# Differential_AS5048_Encoder_Schematic.net
KiCad netlist of a schematic drawn in EAGLE
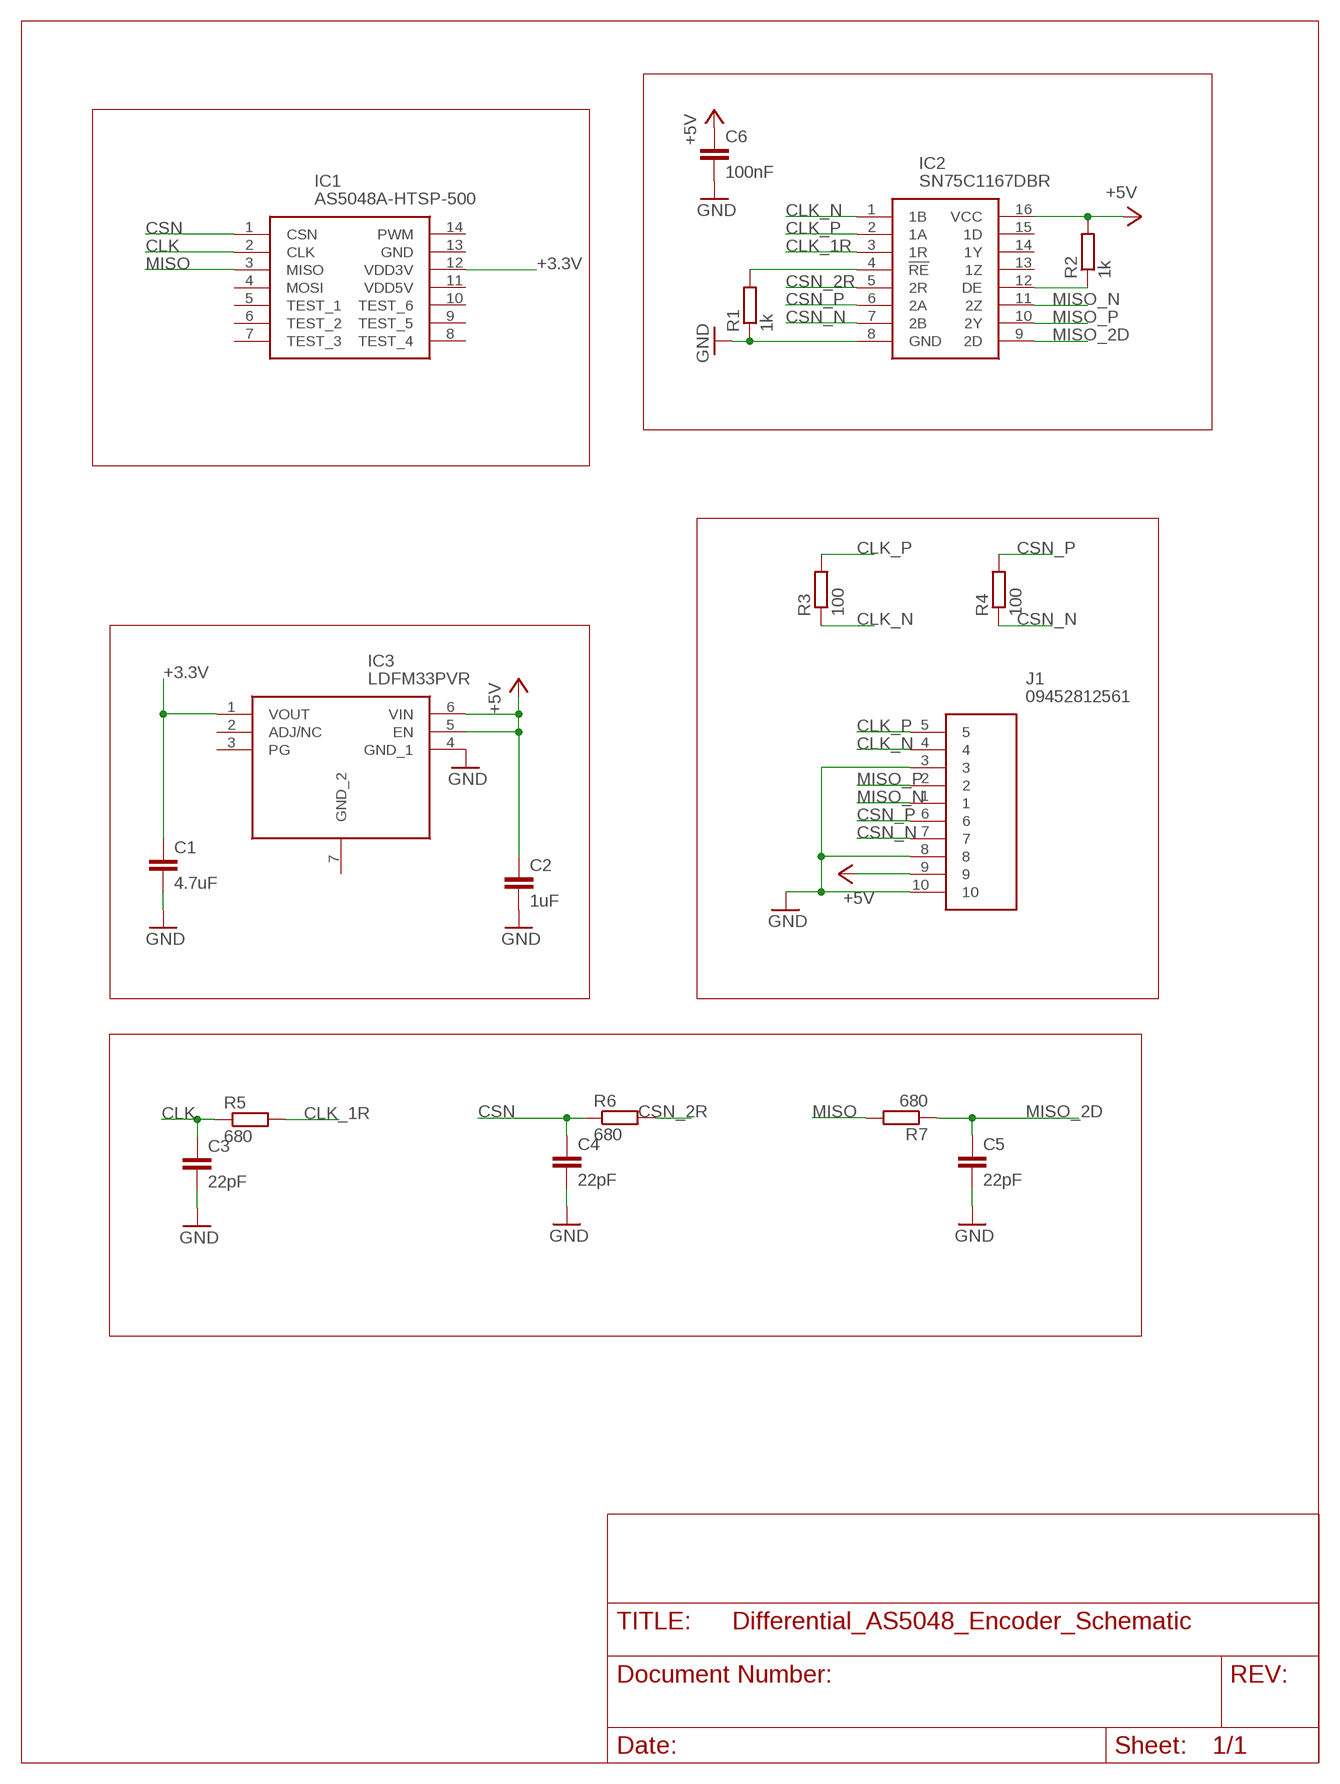
[diagram p0: schematic, sheet 1]

(export (version "E")
  (design (tool "Eeschema 10.0.6"))
  (components
    (comp (ref "C1")
      (value "4.7uF")
      (footprint "eagle-import:C0603")
      (libsource (lib "eagle-import") (part "C-EUC0603"))
    )
    (comp (ref "C2")
      (value "1uF")
      (footprint "eagle-import:C0603")
      (libsource (lib "eagle-import") (part "C-EUC0603"))
    )
    (comp (ref "C3")
      (value "22pF")
      (footprint "eagle-import:C0603")
      (libsource (lib "eagle-import") (part "C-EUC0603"))
    )
    (comp (ref "C4")
      (value "22pF")
      (footprint "eagle-import:C0603")
      (libsource (lib "eagle-import") (part "C-EUC0603"))
    )
    (comp (ref "C5")
      (value "22pF")
      (footprint "eagle-import:C0603")
      (libsource (lib "eagle-import") (part "C-EUC0603"))
    )
    (comp (ref "C6")
      (value "100nF")
      (footprint "eagle-import:C0603")
      (libsource (lib "eagle-import") (part "C-EUC0603"))
    )
    (comp (ref "IC1")
      (value "AS5048A-HTSP-500")
      (footprint "eagle-import:SOP65P640X120-14N")
      (fields (field (name "MOUSER_PART_NUMBER") "985-AS5048A-HTSP-500"))
      (libsource (lib "eagle-import") (part "AS5048A-HTSP-500"))
    )
    (comp (ref "IC2")
      (value "SN75C1167DBR")
      (footprint "eagle-import:SOP65P780X200-16N")
      (fields (field (name "MOUSER_PART_NUMBER") "595-SN75C1167DBR"))
      (libsource (lib "eagle-import") (part "SN75C1167DBR"))
    )
    (comp (ref "IC3")
      (value "LDFM33PVR")
      (footprint "eagle-import:SON65P200X200X100-7N")
      (fields (field (name "MOUSER_PART_NUMBER") "511-LDFM33PVR"))
      (libsource (lib "eagle-import") (part "LDFM33PVR"))
    )
    (comp (ref "J1")
      (value "09452812561")
      (footprint "eagle-import:09452812561")
      (fields (field (name "MOUSER_PART_NUMBER") "617-09452812561"))
      (libsource (lib "eagle-import") (part "09452812561"))
    )
    (comp (ref "R1")
      (value "1k")
      (footprint "eagle-import:R0603")
      (libsource (lib "eagle-import") (part "R-EU_R0603"))
    )
    (comp (ref "R2")
      (value "1k")
      (footprint "eagle-import:R0603")
      (libsource (lib "eagle-import") (part "R-EU_R0603"))
    )
    (comp (ref "R3")
      (value "100")
      (footprint "eagle-import:R0603")
      (libsource (lib "eagle-import") (part "R-EU_R0603"))
    )
    (comp (ref "R4")
      (value "100")
      (footprint "eagle-import:R0603")
      (libsource (lib "eagle-import") (part "R-EU_R0603"))
    )
    (comp (ref "R5")
      (value "680")
      (footprint "eagle-import:R0603")
      (libsource (lib "eagle-import") (part "R-EU_R0603"))
    )
    (comp (ref "R6")
      (value "680")
      (footprint "eagle-import:R0603")
      (libsource (lib "eagle-import") (part "R-EU_R0603"))
    )
    (comp (ref "R7")
      (value "680")
      (footprint "eagle-import:R0603")
      (libsource (lib "eagle-import") (part "R-EU_R0603"))
    )
  )
  (nets
    (net (code "1") (name "+5V") (class "Default")
      (node (ref "C2") (pin "1") (pinfunction "1_1") (pintype "passive"))
      (node (ref "C6") (pin "1") (pinfunction "1_1") (pintype "passive"))
      (node (ref "IC2") (pin "16") (pinfunction "VCC_16") (pintype "bidirectional"))
      (node (ref "IC3") (pin "5") (pinfunction "EN_5") (pintype "bidirectional"))
      (node (ref "IC3") (pin "6") (pinfunction "VIN_6") (pintype "bidirectional"))
      (node (ref "J1") (pin "9") (pinfunction "9_9") (pintype "bidirectional"))
      (node (ref "R2") (pin "2") (pinfunction "2_2") (pintype "passive"))
    )
    (net (code "2") (name "/+3.3V") (class "Default")
      (node (ref "C1") (pin "1") (pinfunction "1_1") (pintype "passive"))
      (node (ref "IC1") (pin "12") (pinfunction "VDD3V_12") (pintype "bidirectional"))
      (node (ref "IC3") (pin "1") (pinfunction "VOUT_1") (pintype "bidirectional"))
    )
    (net (code "3") (name "/CLK") (class "Default")
      (node (ref "C3") (pin "1") (pinfunction "1_1") (pintype "passive"))
      (node (ref "IC1") (pin "2") (pinfunction "CLK_2") (pintype "bidirectional"))
      (node (ref "R5") (pin "1") (pinfunction "1_1") (pintype "passive"))
    )
    (net (code "4") (name "/CLK_1R") (class "Default")
      (node (ref "IC2") (pin "3") (pinfunction "1R_3") (pintype "bidirectional"))
      (node (ref "R5") (pin "2") (pinfunction "2_2") (pintype "passive"))
    )
    (net (code "5") (name "/CLK_N") (class "Default")
      (node (ref "IC2") (pin "1") (pinfunction "1B_1") (pintype "bidirectional"))
      (node (ref "J1") (pin "4") (pinfunction "4_4") (pintype "bidirectional"))
      (node (ref "R3") (pin "1") (pinfunction "1_1") (pintype "passive"))
    )
    (net (code "6") (name "/CLK_P") (class "Default")
      (node (ref "IC2") (pin "2") (pinfunction "1A_2") (pintype "bidirectional"))
      (node (ref "J1") (pin "5") (pinfunction "5_5") (pintype "bidirectional"))
      (node (ref "R3") (pin "2") (pinfunction "2_2") (pintype "passive"))
    )
    (net (code "7") (name "/CSN") (class "Default")
      (node (ref "C4") (pin "1") (pinfunction "1_1") (pintype "passive"))
      (node (ref "IC1") (pin "1") (pinfunction "CSN_1") (pintype "bidirectional"))
      (node (ref "R6") (pin "1") (pinfunction "1_1") (pintype "passive"))
    )
    (net (code "8") (name "/CSN_2R") (class "Default")
      (node (ref "IC2") (pin "5") (pinfunction "2R_5") (pintype "bidirectional"))
      (node (ref "R6") (pin "2") (pinfunction "2_2") (pintype "passive"))
    )
    (net (code "9") (name "/CSN_N") (class "Default")
      (node (ref "IC2") (pin "7") (pinfunction "2B_7") (pintype "bidirectional"))
      (node (ref "J1") (pin "7") (pinfunction "7_7") (pintype "bidirectional"))
      (node (ref "R4") (pin "1") (pinfunction "1_1") (pintype "passive"))
    )
    (net (code "10") (name "/CSN_P") (class "Default")
      (node (ref "IC2") (pin "6") (pinfunction "2A_6") (pintype "bidirectional"))
      (node (ref "J1") (pin "6") (pinfunction "6_6") (pintype "bidirectional"))
      (node (ref "R4") (pin "2") (pinfunction "2_2") (pintype "passive"))
    )
    (net (code "11") (name "/MISO") (class "Default")
      (node (ref "IC1") (pin "3") (pinfunction "MISO_3") (pintype "bidirectional"))
      (node (ref "R7") (pin "2") (pinfunction "2_2") (pintype "passive"))
    )
    (net (code "12") (name "/MISO_2D") (class "Default")
      (node (ref "C5") (pin "1") (pinfunction "1_1") (pintype "passive"))
      (node (ref "IC2") (pin "9") (pinfunction "2D_9") (pintype "bidirectional"))
      (node (ref "R7") (pin "1") (pinfunction "1_1") (pintype "passive"))
    )
    (net (code "13") (name "/MISO_N") (class "Default")
      (node (ref "IC2") (pin "11") (pinfunction "2Z_11") (pintype "bidirectional"))
      (node (ref "J1") (pin "1") (pinfunction "1_1") (pintype "bidirectional"))
    )
    (net (code "14") (name "/MISO_P") (class "Default")
      (node (ref "IC2") (pin "10") (pinfunction "2Y_10") (pintype "bidirectional"))
      (node (ref "J1") (pin "2") (pinfunction "2_2") (pintype "bidirectional"))
    )
    (net (code "15") (name "GND") (class "Default")
      (node (ref "C1") (pin "2") (pinfunction "2_2") (pintype "passive"))
      (node (ref "C2") (pin "2") (pinfunction "2_2") (pintype "passive"))
      (node (ref "C3") (pin "2") (pinfunction "2_2") (pintype "passive"))
      (node (ref "C4") (pin "2") (pinfunction "2_2") (pintype "passive"))
      (node (ref "C5") (pin "2") (pinfunction "2_2") (pintype "passive"))
      (node (ref "C6") (pin "2") (pinfunction "2_2") (pintype "passive"))
      (node (ref "IC2") (pin "8") (pinfunction "GND_8") (pintype "bidirectional"))
      (node (ref "IC3") (pin "4") (pinfunction "GND_1_4") (pintype "bidirectional"))
      (node (ref "J1") (pin "10") (pinfunction "10_10") (pintype "bidirectional"))
      (node (ref "J1") (pin "3") (pinfunction "3_3") (pintype "bidirectional"))
      (node (ref "J1") (pin "8") (pinfunction "8_8") (pintype "bidirectional"))
      (node (ref "R1") (pin "1") (pinfunction "1_1") (pintype "passive"))
    )
    (net (code "16") (name "Net-(IC2-DE)") (class "Default")
      (node (ref "IC2") (pin "12") (pinfunction "DE_12") (pintype "bidirectional"))
      (node (ref "R2") (pin "1") (pinfunction "1_1") (pintype "passive"))
    )
    (net (code "17") (name "Net-(IC2-~{RE})") (class "Default")
      (node (ref "IC2") (pin "4") (pinfunction "~{RE}_4") (pintype "bidirectional"))
      (node (ref "R1") (pin "2") (pinfunction "2_2") (pintype "passive"))
    )
    (net (code "18") (name "unconnected-(IC1-GND-Pad13)") (class "Default")
      (node (ref "IC1") (pin "13") (pinfunction "GND_13") (pintype "bidirectional"))
    )
    (net (code "19") (name "unconnected-(IC1-MOSI-Pad4)") (class "Default")
      (node (ref "IC1") (pin "4") (pinfunction "MOSI_4") (pintype "bidirectional"))
    )
    (net (code "20") (name "unconnected-(IC1-PWM-Pad14)") (class "Default")
      (node (ref "IC1") (pin "14") (pinfunction "PWM_14") (pintype "bidirectional"))
    )
    (net (code "21") (name "unconnected-(IC1-TEST_1-Pad5)") (class "Default")
      (node (ref "IC1") (pin "5") (pinfunction "TEST_1_5") (pintype "bidirectional"))
    )
    (net (code "22") (name "unconnected-(IC1-TEST_2-Pad6)") (class "Default")
      (node (ref "IC1") (pin "6") (pinfunction "TEST_2_6") (pintype "bidirectional"))
    )
    (net (code "23") (name "unconnected-(IC1-TEST_3-Pad7)") (class "Default")
      (node (ref "IC1") (pin "7") (pinfunction "TEST_3_7") (pintype "bidirectional"))
    )
    (net (code "24") (name "unconnected-(IC1-TEST_4-Pad8)") (class "Default")
      (node (ref "IC1") (pin "8") (pinfunction "TEST_4_8") (pintype "bidirectional"))
    )
    (net (code "25") (name "unconnected-(IC1-TEST_5-Pad9)") (class "Default")
      (node (ref "IC1") (pin "9") (pinfunction "TEST_5_9") (pintype "bidirectional"))
    )
    (net (code "26") (name "unconnected-(IC1-TEST_6-Pad10)") (class "Default")
      (node (ref "IC1") (pin "10") (pinfunction "TEST_6_10") (pintype "bidirectional"))
    )
    (net (code "27") (name "unconnected-(IC1-VDD5V-Pad11)") (class "Default")
      (node (ref "IC1") (pin "11") (pinfunction "VDD5V_11") (pintype "bidirectional"))
    )
    (net (code "28") (name "unconnected-(IC2-1D-Pad15)") (class "Default")
      (node (ref "IC2") (pin "15") (pinfunction "1D_15") (pintype "bidirectional"))
    )
    (net (code "29") (name "unconnected-(IC2-1Y-Pad14)") (class "Default")
      (node (ref "IC2") (pin "14") (pinfunction "1Y_14") (pintype "bidirectional"))
    )
    (net (code "30") (name "unconnected-(IC2-1Z-Pad13)") (class "Default")
      (node (ref "IC2") (pin "13") (pinfunction "1Z_13") (pintype "bidirectional"))
    )
    (net (code "31") (name "unconnected-(IC3-ADJ{slash}NC-Pad2)") (class "Default")
      (node (ref "IC3") (pin "2") (pinfunction "ADJ/NC_2") (pintype "bidirectional"))
    )
    (net (code "32") (name "unconnected-(IC3-GND_2-Pad7)") (class "Default")
      (node (ref "IC3") (pin "7") (pinfunction "GND_2_7") (pintype "bidirectional"))
    )
    (net (code "33") (name "unconnected-(IC3-PG-Pad3)") (class "Default")
      (node (ref "IC3") (pin "3") (pinfunction "PG_3") (pintype "bidirectional"))
    )
  )
)
